# syringe_board_2_1.net
KiCad netlist of a schematic drawn in EAGLE
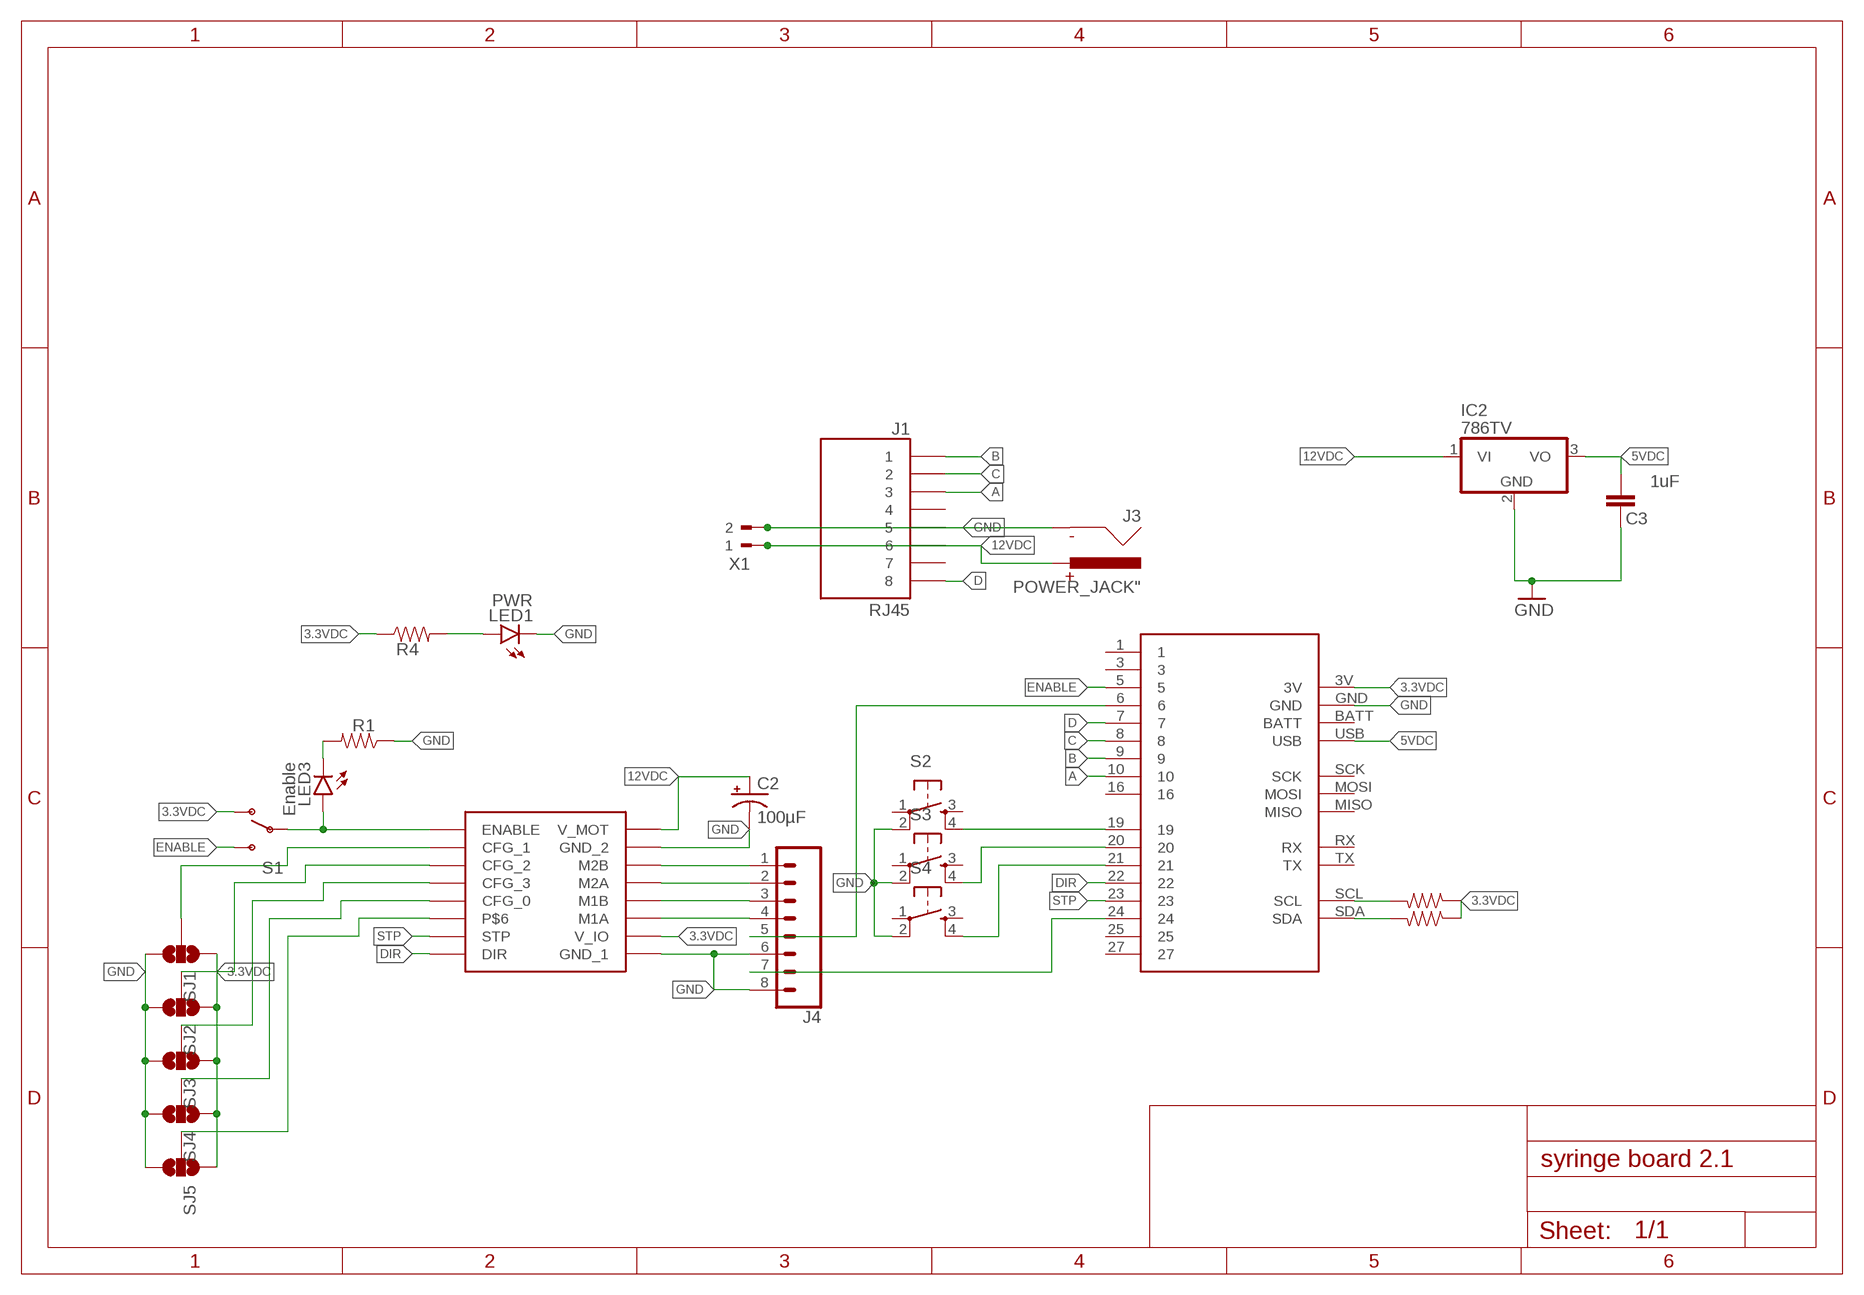
[diagram p0: schematic, sheet 1]

(export (version "E")
  (design (tool "Eeschema 10.0.6"))
  (components
    (comp (ref "C2")
      (value "100µF")
      (footprint "eagle-import:PANASONIC_D")
      (libsource (lib "eagle-import") (part "CPOL-USD"))
    )
    (comp (ref "C3")
      (value "1uF")
      (footprint "eagle-import:0603-CAP")
      (libsource (lib "eagle-import") (part "CAP0603-CAP"))
    )
    (comp (ref "IC2")
      (value "786TV")
      (footprint "eagle-import:TO220V")
      (libsource (lib "eagle-import") (part "78TV6"))
    )
    (comp (ref "J1")
      (value "RJ45")
      (footprint "eagle-import:RJ45-8")
      (libsource (lib "eagle-import") (part "RJ45"))
    )
    (comp (ref "J3")
      (value "POWER_JACK\"")
      (footprint "eagle-import:BARREL_CONN")
      (fields (field (name "MANUFACTURER") "CUI Inc"))
      (libsource (lib "eagle-import") (part "POWER_JACK{dblquote}"))
    )
    (comp (ref "J4")
      (value "CONN_08NO_SILK_FEMALE_PTH")
      (footprint "eagle-import:1X08_NO_SILK")
      (libsource (lib "eagle-import") (part "CONN_08NO_SILK_FEMALE_PTH"))
    )
    (comp (ref "LED1")
      (value "PWR")
      (footprint "eagle-import:LED-0603")
      (libsource (lib "eagle-import") (part "LED0603"))
    )
    (comp (ref "LED3")
      (value "Enable")
      (footprint "eagle-import:LED-0603")
      (libsource (lib "eagle-import") (part "LED0603"))
    )
    (comp (ref "R1")
      (value "RESISTOR0603")
      (footprint "eagle-import:0603")
      (libsource (lib "eagle-import") (part "RESISTOR0603"))
    )
    (comp (ref "R4")
      (value "RESISTOR0603")
      (footprint "eagle-import:0603")
      (libsource (lib "eagle-import") (part "RESISTOR0603"))
    )
    (comp (ref "R17")
      (value "RESISTOR0603")
      (footprint "eagle-import:0603")
      (libsource (lib "eagle-import") (part "RESISTOR0603"))
    )
    (comp (ref "R20")
      (value "RESISTOR0603")
      (footprint "eagle-import:0603")
      (libsource (lib "eagle-import") (part "RESISTOR0603"))
    )
    (comp (ref "S1")
      (value "SWITCH-SPDTVERTICAL_TOGGLE")
      (footprint "eagle-import:VERT_TOGGLE")
      (libsource (lib "eagle-import") (part "SWITCH-SPDTVERTICAL_TOGGLE"))
    )
    (comp (ref "S2")
      (value "TAC_SWITCHSMD")
      (footprint "eagle-import:TACTILE-PTH")
      (libsource (lib "eagle-import") (part "TAC_SWITCHPTH"))
    )
    (comp (ref "S3")
      (value "TAC_SWITCHSMD")
      (footprint "eagle-import:TACTILE-PTH")
      (libsource (lib "eagle-import") (part "TAC_SWITCHPTH"))
    )
    (comp (ref "S4")
      (value "TAC_SWITCHSMD")
      (footprint "eagle-import:TACTILE-PTH")
      (libsource (lib "eagle-import") (part "TAC_SWITCHPTH"))
    )
    (comp (ref "SJ1")
      (value "SOLDERJUMPER_2WAYS")
      (footprint "eagle-import:SJ_3")
      (libsource (lib "eagle-import") (part "SOLDERJUMPER_2WAYS"))
    )
    (comp (ref "SJ2")
      (value "SOLDERJUMPER_2WAYS")
      (footprint "eagle-import:SJ_3")
      (libsource (lib "eagle-import") (part "SOLDERJUMPER_2WAYS"))
    )
    (comp (ref "SJ3")
      (value "SOLDERJUMPER_2WAYS")
      (footprint "eagle-import:SJ_3")
      (libsource (lib "eagle-import") (part "SOLDERJUMPER_2WAYS"))
    )
    (comp (ref "SJ4")
      (value "SOLDERJUMPER_2WAYS")
      (footprint "eagle-import:SJ_3")
      (libsource (lib "eagle-import") (part "SOLDERJUMPER_2WAYS"))
    )
    (comp (ref "SJ5")
      (value "SOLDERJUMPER_2WAYS")
      (footprint "eagle-import:SJ_3")
      (libsource (lib "eagle-import") (part "SOLDERJUMPER_2WAYS"))
    )
    (comp (ref "U$1")
      (value "SILENT_STEP_STICK")
      (footprint "eagle-import:SILENT_STEP_STICK")
      (libsource (lib "eagle-import") (part "SILENT_STEP_STICK"))
    )
    (comp (ref "U$2")
      (value "FEATHERFEAT")
      (footprint "eagle-import:FEATHER")
      (libsource (lib "eagle-import") (part "FEATHERFEAT"))
    )
    (comp (ref "X1")
      (value "90-2")
      (footprint "eagle-import:90-2")
      (libsource (lib "eagle-import") (part "90-2"))
    )
  )
  (nets
    (net (code "1") (name "3.3VDC") (class "Default")
      (node (ref "R17") (pin "1") (pinfunction "1_1") (pintype "passive"))
      (node (ref "R20") (pin "1") (pinfunction "1_1") (pintype "passive"))
      (node (ref "R4") (pin "1") (pinfunction "1_1") (pintype "passive"))
      (node (ref "S1") (pin "P$1") (pinfunction "O_P$1") (pintype "passive"))
      (node (ref "SJ1") (pin "1") (pinfunction "1_1") (pintype "passive"))
      (node (ref "SJ2") (pin "1") (pinfunction "1_1") (pintype "passive"))
      (node (ref "SJ3") (pin "1") (pinfunction "1_1") (pintype "passive"))
      (node (ref "SJ4") (pin "1") (pinfunction "1_1") (pintype "passive"))
      (node (ref "SJ5") (pin "1") (pinfunction "1_1") (pintype "passive"))
      (node (ref "U$1") (pin "V_IO") (pinfunction "V_IO_V_IO") (pintype "bidirectional"))
      (node (ref "U$2") (pin "3V") (pinfunction "3V_3V") (pintype "bidirectional"))
    )
    (net (code "2") (name "5VDC") (class "Default")
      (node (ref "C3") (pin "2") (pinfunction "2_2") (pintype "passive"))
      (node (ref "IC2") (pin "3") (pinfunction "VO_3") (pintype "passive"))
      (node (ref "U$2") (pin "USB") (pinfunction "USB_USB") (pintype "bidirectional"))
    )
    (net (code "3") (name "12VDC") (class "Default")
      (node (ref "C2") (pin "+") (pinfunction "+_+") (pintype "passive"))
      (node (ref "IC2") (pin "1") (pinfunction "VI_1") (pintype "input"))
      (node (ref "J1") (pin "6") (pinfunction "6_6") (pintype "bidirectional"))
      (node (ref "J3") (pin "PWR") (pinfunction "PWR_PWR") (pintype "bidirectional"))
      (node (ref "U$1") (pin "V_MOT") (pinfunction "V_MOT_V_MOT") (pintype "bidirectional"))
      (node (ref "X1") (pin "1") (pinfunction "1_1") (pintype "passive"))
    )
    (net (code "4") (name "A") (class "Default")
      (node (ref "J1") (pin "3") (pinfunction "3_3") (pintype "bidirectional"))
      (node (ref "U$2") (pin "10") (pinfunction "10_10") (pintype "bidirectional"))
    )
    (net (code "5") (name "B") (class "Default")
      (node (ref "J1") (pin "1") (pinfunction "1_1") (pintype "bidirectional"))
      (node (ref "U$2") (pin "9") (pinfunction "9_9") (pintype "bidirectional"))
    )
    (net (code "6") (name "C") (class "Default")
      (node (ref "J1") (pin "2") (pinfunction "2_2") (pintype "bidirectional"))
      (node (ref "U$2") (pin "8") (pinfunction "8_8") (pintype "bidirectional"))
    )
    (net (code "7") (name "D") (class "Default")
      (node (ref "J1") (pin "8") (pinfunction "8_8") (pintype "bidirectional"))
      (node (ref "U$2") (pin "7") (pinfunction "7_7") (pintype "bidirectional"))
    )
    (net (code "8") (name "DIR") (class "Default")
      (node (ref "U$1") (pin "DIR") (pinfunction "DIR_DIR") (pintype "bidirectional"))
      (node (ref "U$2") (pin "22") (pinfunction "22_22") (pintype "bidirectional"))
    )
    (net (code "9") (name "ENABLE") (class "Default")
      (node (ref "S1") (pin "P$3") (pinfunction "S_P$3") (pintype "passive"))
      (node (ref "U$2") (pin "5") (pinfunction "5_5") (pintype "bidirectional"))
    )
    (net (code "10") (name "GND") (class "Default")
      (node (ref "C2") (pin "-") (pinfunction "-_-") (pintype "passive"))
      (node (ref "C3") (pin "1") (pinfunction "1_1") (pintype "passive"))
      (node (ref "IC2") (pin "2") (pinfunction "GND_2") (pintype "passive"))
      (node (ref "J1") (pin "5") (pinfunction "5_5") (pintype "bidirectional"))
      (node (ref "J3") (pin "GND") (pinfunction "GND_GND") (pintype "bidirectional"))
      (node (ref "J4") (pin "6") (pinfunction "6_6") (pintype "passive"))
      (node (ref "J4") (pin "8") (pinfunction "8_8") (pintype "passive"))
      (node (ref "LED1") (pin "C") (pinfunction "C_C") (pintype "passive"))
      (node (ref "R1") (pin "1") (pinfunction "1_1") (pintype "passive"))
      (node (ref "S2") (pin "2") (pinfunction "2_2") (pintype "passive"))
      (node (ref "S3") (pin "2") (pinfunction "2_2") (pintype "passive"))
      (node (ref "S4") (pin "2") (pinfunction "2_2") (pintype "passive"))
      (node (ref "SJ1") (pin "3") (pinfunction "3_3") (pintype "passive"))
      (node (ref "SJ2") (pin "3") (pinfunction "3_3") (pintype "passive"))
      (node (ref "SJ3") (pin "3") (pinfunction "3_3") (pintype "passive"))
      (node (ref "SJ4") (pin "3") (pinfunction "3_3") (pintype "passive"))
      (node (ref "SJ5") (pin "3") (pinfunction "3_3") (pintype "passive"))
      (node (ref "U$1") (pin "G_1") (pinfunction "GND_1_G_1") (pintype "bidirectional"))
      (node (ref "U$1") (pin "G_2") (pinfunction "GND_2_G_2") (pintype "bidirectional"))
      (node (ref "U$2") (pin "GND") (pinfunction "GND_GND") (pintype "bidirectional"))
      (node (ref "X1") (pin "2") (pinfunction "2_2") (pintype "passive"))
    )
    (net (code "11") (name "Net-(J4-Pad1)") (class "Default")
      (node (ref "J4") (pin "1") (pinfunction "1_1") (pintype "passive"))
      (node (ref "U$1") (pin "M2B") (pinfunction "M2B_M2B") (pintype "bidirectional"))
    )
    (net (code "12") (name "Net-(J4-Pad2)") (class "Default")
      (node (ref "J4") (pin "2") (pinfunction "2_2") (pintype "passive"))
      (node (ref "U$1") (pin "M2A") (pinfunction "M2A_M2A") (pintype "bidirectional"))
    )
    (net (code "13") (name "Net-(J4-Pad3)") (class "Default")
      (node (ref "J4") (pin "3") (pinfunction "3_3") (pintype "passive"))
      (node (ref "U$1") (pin "M1B") (pinfunction "M1B_M1B") (pintype "bidirectional"))
    )
    (net (code "14") (name "Net-(J4-Pad4)") (class "Default")
      (node (ref "J4") (pin "4") (pinfunction "4_4") (pintype "passive"))
      (node (ref "U$1") (pin "M1A") (pinfunction "M1A_M1A") (pintype "bidirectional"))
    )
    (net (code "15") (name "Net-(J4-Pad5)") (class "Default")
      (node (ref "J4") (pin "5") (pinfunction "5_5") (pintype "passive"))
      (node (ref "U$2") (pin "6") (pinfunction "6_6") (pintype "bidirectional"))
    )
    (net (code "16") (name "Net-(J4-Pad7)") (class "Default")
      (node (ref "J4") (pin "7") (pinfunction "7_7") (pintype "passive"))
      (node (ref "U$2") (pin "24") (pinfunction "24_24") (pintype "bidirectional"))
    )
    (net (code "17") (name "Net-(LED1-PadA)") (class "Default")
      (node (ref "LED1") (pin "A") (pinfunction "A_A") (pintype "passive"))
      (node (ref "R4") (pin "2") (pinfunction "2_2") (pintype "passive"))
    )
    (net (code "18") (name "Net-(LED3-PadC)") (class "Default")
      (node (ref "LED3") (pin "C") (pinfunction "C_C") (pintype "passive"))
      (node (ref "R1") (pin "2") (pinfunction "2_2") (pintype "passive"))
    )
    (net (code "19") (name "Net-(R17-Pad2)") (class "Default")
      (node (ref "R17") (pin "2") (pinfunction "2_2") (pintype "passive"))
      (node (ref "U$2") (pin "SCL") (pinfunction "SCL_SCL") (pintype "bidirectional"))
    )
    (net (code "20") (name "Net-(R20-Pad2)") (class "Default")
      (node (ref "R20") (pin "2") (pinfunction "2_2") (pintype "passive"))
      (node (ref "U$2") (pin "SDA") (pinfunction "SDA_SDA") (pintype "bidirectional"))
    )
    (net (code "21") (name "Net-(S1-P)") (class "Default")
      (node (ref "LED3") (pin "A") (pinfunction "A_A") (pintype "passive"))
      (node (ref "S1") (pin "P$2") (pinfunction "P_P$2") (pintype "passive"))
      (node (ref "U$1") (pin "ENABLE") (pinfunction "ENABLE_ENABLE") (pintype "bidirectional"))
    )
    (net (code "22") (name "Net-(S2-Pad4)") (class "Default")
      (node (ref "S2") (pin "4") (pinfunction "4_4") (pintype "passive"))
      (node (ref "U$2") (pin "19") (pinfunction "19_19") (pintype "bidirectional"))
    )
    (net (code "23") (name "Net-(S3-Pad4)") (class "Default")
      (node (ref "S3") (pin "4") (pinfunction "4_4") (pintype "passive"))
      (node (ref "U$2") (pin "20") (pinfunction "20_20") (pintype "bidirectional"))
    )
    (net (code "24") (name "Net-(S4-Pad4)") (class "Default")
      (node (ref "S4") (pin "4") (pinfunction "4_4") (pintype "passive"))
      (node (ref "U$2") (pin "21") (pinfunction "21_21") (pintype "bidirectional"))
    )
    (net (code "25") (name "Net-(SJ1-Pad2)") (class "Default")
      (node (ref "SJ1") (pin "2") (pinfunction "2_2") (pintype "passive"))
      (node (ref "U$1") (pin "CFG_1") (pinfunction "CFG_1_CFG_1") (pintype "bidirectional"))
    )
    (net (code "26") (name "Net-(SJ2-Pad2)") (class "Default")
      (node (ref "SJ2") (pin "2") (pinfunction "2_2") (pintype "passive"))
      (node (ref "U$1") (pin "CFG_2") (pinfunction "CFG_2_CFG_2") (pintype "bidirectional"))
    )
    (net (code "27") (name "Net-(SJ3-Pad2)") (class "Default")
      (node (ref "SJ3") (pin "2") (pinfunction "2_2") (pintype "passive"))
      (node (ref "U$1") (pin "CFG_3") (pinfunction "CFG_3_CFG_3") (pintype "bidirectional"))
    )
    (net (code "28") (name "Net-(SJ4-Pad2)") (class "Default")
      (node (ref "SJ4") (pin "2") (pinfunction "2_2") (pintype "passive"))
      (node (ref "U$1") (pin "CFG_0") (pinfunction "CFG_0_CFG_0") (pintype "bidirectional"))
    )
    (net (code "29") (name "Net-(SJ5-Pad2)") (class "Default")
      (node (ref "SJ5") (pin "2") (pinfunction "2_2") (pintype "passive"))
      (node (ref "U$1") (pin "P$6") (pinfunction "P$6_P$6") (pintype "bidirectional"))
    )
    (net (code "30") (name "STP") (class "Default")
      (node (ref "U$1") (pin "STP") (pinfunction "STP_STP") (pintype "bidirectional"))
      (node (ref "U$2") (pin "23") (pinfunction "23_23") (pintype "bidirectional"))
    )
    (net (code "31") (name "unconnected-(J1-Pad4)") (class "Default")
      (node (ref "J1") (pin "4") (pinfunction "4_4") (pintype "bidirectional"))
    )
    (net (code "32") (name "unconnected-(J1-Pad7)") (class "Default")
      (node (ref "J1") (pin "7") (pinfunction "7_7") (pintype "bidirectional"))
    )
    (net (code "33") (name "unconnected-(S2-Pad1)") (class "Default")
      (node (ref "S2") (pin "1") (pinfunction "1_1") (pintype "passive"))
    )
    (net (code "34") (name "unconnected-(S2-Pad3)") (class "Default")
      (node (ref "S2") (pin "3") (pinfunction "3_3") (pintype "passive"))
    )
    (net (code "35") (name "unconnected-(S3-Pad1)") (class "Default")
      (node (ref "S3") (pin "1") (pinfunction "1_1") (pintype "passive"))
    )
    (net (code "36") (name "unconnected-(S3-Pad3)") (class "Default")
      (node (ref "S3") (pin "3") (pinfunction "3_3") (pintype "passive"))
    )
    (net (code "37") (name "unconnected-(S4-Pad1)") (class "Default")
      (node (ref "S4") (pin "1") (pinfunction "1_1") (pintype "passive"))
    )
    (net (code "38") (name "unconnected-(S4-Pad3)") (class "Default")
      (node (ref "S4") (pin "3") (pinfunction "3_3") (pintype "passive"))
    )
    (net (code "39") (name "unconnected-(U$2-Pad1)") (class "Default")
      (node (ref "U$2") (pin "1") (pinfunction "1_1") (pintype "bidirectional"))
    )
    (net (code "40") (name "unconnected-(U$2-Pad3)") (class "Default")
      (node (ref "U$2") (pin "3") (pinfunction "3_3") (pintype "bidirectional"))
    )
    (net (code "41") (name "unconnected-(U$2-Pad16)") (class "Default")
      (node (ref "U$2") (pin "16") (pinfunction "16_16") (pintype "bidirectional"))
    )
    (net (code "42") (name "unconnected-(U$2-Pad25)") (class "Default")
      (node (ref "U$2") (pin "25") (pinfunction "25_25") (pintype "bidirectional"))
    )
    (net (code "43") (name "unconnected-(U$2-Pad27)") (class "Default")
      (node (ref "U$2") (pin "27") (pinfunction "27_27") (pintype "bidirectional"))
    )
    (net (code "44") (name "unconnected-(U$2-PadBATT)") (class "Default")
      (node (ref "U$2") (pin "BATT") (pinfunction "BATT_BATT") (pintype "bidirectional"))
    )
    (net (code "45") (name "unconnected-(U$2-PadMISO)") (class "Default")
      (node (ref "U$2") (pin "MISO") (pinfunction "MISO_MISO") (pintype "bidirectional"))
    )
    (net (code "46") (name "unconnected-(U$2-PadMOSI)") (class "Default")
      (node (ref "U$2") (pin "MOSI") (pinfunction "MOSI_MOSI") (pintype "bidirectional"))
    )
    (net (code "47") (name "unconnected-(U$2-PadRX)") (class "Default")
      (node (ref "U$2") (pin "RX") (pinfunction "RX_RX") (pintype "bidirectional"))
    )
    (net (code "48") (name "unconnected-(U$2-PadSCK)") (class "Default")
      (node (ref "U$2") (pin "SCK") (pinfunction "SCK_SCK") (pintype "bidirectional"))
    )
    (net (code "49") (name "unconnected-(U$2-PadTX)") (class "Default")
      (node (ref "U$2") (pin "TX") (pinfunction "TX_TX") (pintype "bidirectional"))
    )
  )
)
